# IO.net
KiCad netlist of a schematic drawn in Altium Designer
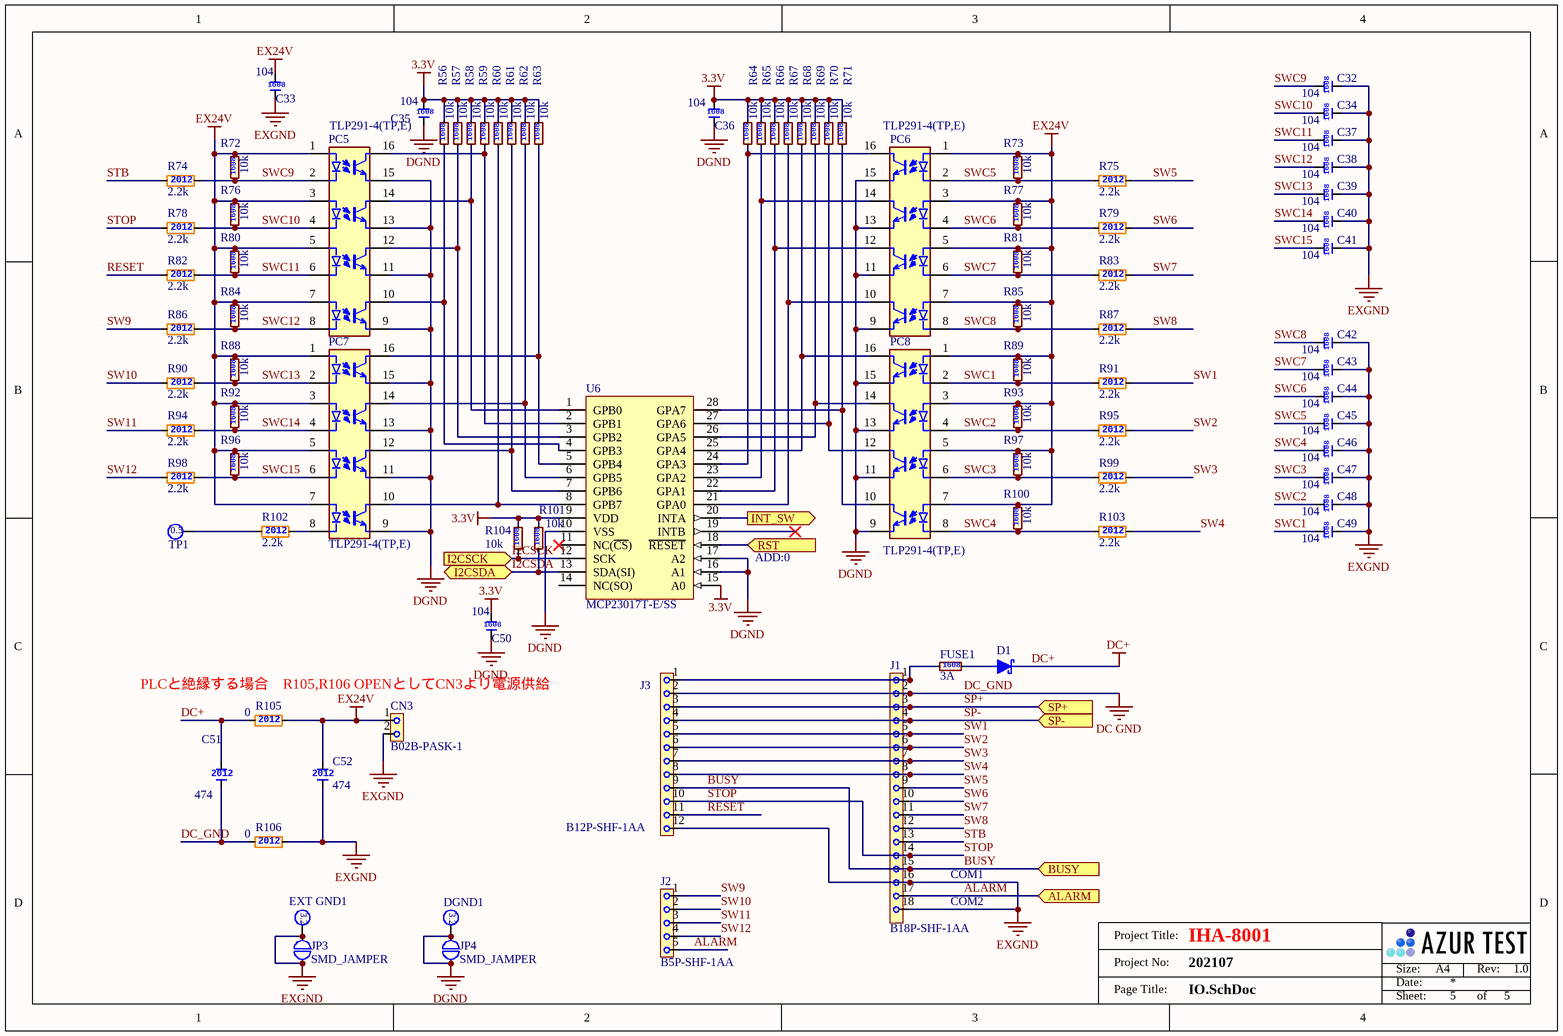
[diagram p0: IO.SchDoc]

(export (version "E")
  (design (tool "Eeschema 10.0.6"))
  (components
    (comp (ref "C32")
      (value "CGA3E2X7R1H104K080AA")
      (footprint "C1608")
      (description "セラコン1608サイズ")
      (fields (field (name "TAG") "104") (field (name "VOLTAGE") "50V"))
      (libsource (lib "Audio") (part "C1608"))
    )
    (comp (ref "C33")
      (value "CGA3E2X7R1H104K080AA")
      (footprint "C1608")
      (description "セラコン1608サイズ")
      (fields (field (name "TAG") "104") (field (name "VOLTAGE") "50V"))
      (libsource (lib "Audio") (part "C1608"))
    )
    (comp (ref "C34")
      (value "CGA3E2X7R1H104K080AA")
      (footprint "C1608")
      (description "セラコン1608サイズ")
      (fields (field (name "TAG") "104") (field (name "VOLTAGE") "50V"))
      (libsource (lib "Audio") (part "C1608"))
    )
    (comp (ref "C35")
      (value "CGA3E2X7R1H104K080AA")
      (footprint "C1608")
      (description "セラコン1608サイズ")
      (fields (field (name "TAG") "104") (field (name "VOLTAGE") "50V"))
      (libsource (lib "Audio") (part "C1608"))
    )
    (comp (ref "C36")
      (value "CGA3E2X7R1H104K080AA")
      (footprint "C1608")
      (description "セラコン1608サイズ")
      (fields (field (name "TAG") "104") (field (name "VOLTAGE") "50V"))
      (libsource (lib "Audio") (part "C1608"))
    )
    (comp (ref "C37")
      (value "CGA3E2X7R1H104K080AA")
      (footprint "C1608")
      (description "セラコン1608サイズ")
      (fields (field (name "TAG") "104") (field (name "VOLTAGE") "50V"))
      (libsource (lib "Audio") (part "C1608"))
    )
    (comp (ref "C38")
      (value "CGA3E2X7R1H104K080AA")
      (footprint "C1608")
      (description "セラコン1608サイズ")
      (fields (field (name "TAG") "104") (field (name "VOLTAGE") "50V"))
      (libsource (lib "Audio") (part "C1608"))
    )
    (comp (ref "C39")
      (value "CGA3E2X7R1H104K080AA")
      (footprint "C1608")
      (description "セラコン1608サイズ")
      (fields (field (name "TAG") "104") (field (name "VOLTAGE") "50V"))
      (libsource (lib "Audio") (part "C1608"))
    )
    (comp (ref "C40")
      (value "CGA3E2X7R1H104K080AA")
      (footprint "C1608")
      (description "セラコン1608サイズ")
      (fields (field (name "TAG") "104") (field (name "VOLTAGE") "50V"))
      (libsource (lib "Audio") (part "C1608"))
    )
    (comp (ref "C41")
      (value "CGA3E2X7R1H104K080AA")
      (footprint "C1608")
      (description "セラコン1608サイズ")
      (fields (field (name "TAG") "104") (field (name "VOLTAGE") "50V"))
      (libsource (lib "Audio") (part "C1608"))
    )
    (comp (ref "C42")
      (value "CGA3E2X7R1H104K080AA")
      (footprint "C1608")
      (description "セラコン1608サイズ")
      (fields (field (name "TAG") "104") (field (name "VOLTAGE") "50V"))
      (libsource (lib "Audio") (part "C1608"))
    )
    (comp (ref "C43")
      (value "CGA3E2X7R1H104K080AA")
      (footprint "C1608")
      (description "セラコン1608サイズ")
      (fields (field (name "TAG") "104") (field (name "VOLTAGE") "50V"))
      (libsource (lib "Audio") (part "C1608"))
    )
    (comp (ref "C44")
      (value "CGA3E2X7R1H104K080AA")
      (footprint "C1608")
      (description "セラコン1608サイズ")
      (fields (field (name "TAG") "104") (field (name "VOLTAGE") "50V"))
      (libsource (lib "Audio") (part "C1608"))
    )
    (comp (ref "C45")
      (value "CGA3E2X7R1H104K080AA")
      (footprint "C1608")
      (description "セラコン1608サイズ")
      (fields (field (name "TAG") "104") (field (name "VOLTAGE") "50V"))
      (libsource (lib "Audio") (part "C1608"))
    )
    (comp (ref "C46")
      (value "CGA3E2X7R1H104K080AA")
      (footprint "C1608")
      (description "セラコン1608サイズ")
      (fields (field (name "TAG") "104") (field (name "VOLTAGE") "50V"))
      (libsource (lib "Audio") (part "C1608"))
    )
    (comp (ref "C47")
      (value "CGA3E2X7R1H104K080AA")
      (footprint "C1608")
      (description "セラコン1608サイズ")
      (fields (field (name "TAG") "104") (field (name "VOLTAGE") "50V"))
      (libsource (lib "Audio") (part "C1608"))
    )
    (comp (ref "C48")
      (value "CGA3E2X7R1H104K080AA")
      (footprint "C1608")
      (description "セラコン1608サイズ")
      (fields (field (name "TAG") "104") (field (name "VOLTAGE") "50V"))
      (libsource (lib "Audio") (part "C1608"))
    )
    (comp (ref "C49")
      (value "CGA3E2X7R1H104K080AA")
      (footprint "C1608")
      (description "セラコン1608サイズ")
      (fields (field (name "TAG") "104") (field (name "VOLTAGE") "50V"))
      (libsource (lib "Audio") (part "C1608"))
    )
    (comp (ref "C50")
      (value "CGA3E2X7R1H104K080AA")
      (footprint "C1608")
      (description "セラコン1608サイズ")
      (fields (field (name "TAG") "104") (field (name "VOLTAGE") "50V"))
      (libsource (lib "Audio") (part "C1608"))
    )
    (comp (ref "C51")
      (value "GRM21BR71H474MA88")
      (footprint "C2012")
      (description "セラコン2012サイズ")
      (fields (field (name "TAG") "474") (field (name "VOLTAGE") "50V"))
      (libsource (lib "Audio") (part "C2012"))
    )
    (comp (ref "C52")
      (value "GRM21BR71H474MA88")
      (footprint "C2012")
      (description "セラコン2012サイズ")
      (fields (field (name "TAG") "474") (field (name "VOLTAGE") "50V"))
      (libsource (lib "Audio") (part "C2012"))
    )
    (comp (ref "CN3")
      (value "B02B-PASK-1")
      (footprint "B02B-PASK-1")
      (description "雄,ストレート,1列2ピン")
      (libsource (lib "Audio Prj") (part "B02B-PASK-1"))
    )
    (comp (ref "D1")
      (value "SIPS3150U")
      (footprint "DO-214AA")
      (description "Schottky Rectifier")
      (fields (field (name "VOLTAGE") "150V"))
      (libsource (lib "Audio") (part "Diode SMB 5.4x4.3"))
    )
    (comp (ref "DGND1")
      (value "TP3.2mm")
      (footprint "TP3.2mm")
      (description "Test-Point 3.2mm")
      (libsource (lib "Audio Prj") (part "TP3.2mm"))
    )
    (comp (ref "EXT GND1")
      (value "TP3.2mm")
      (footprint "TP3.2mm")
      (description "Test-Point 3.2mm")
      (libsource (lib "Audio Prj") (part "TP3.2mm"))
    )
    (comp (ref "FUSE1")
      (value "ERB-RE3R00V")
      (footprint "R1608")
      (description "3A 1608サイズ")
      (fields (field (name "TAG") "3A"))
      (libsource (lib "") (part "TF1608_1"))
    )
    (comp (ref "J1")
      (value "B18P-SHF-1AA")
      (footprint "B18P-SHF-1AA")
      (description "雄,ストレート,1列12ピン PCB")
      (libsource (lib "Audio Prj") (part "B18P-SHF-1AA"))
    )
    (comp (ref "J2")
      (value "B5P-SHF-1AA")
      (footprint "B5P-SHF-1AA")
      (description "雄,ストレート,1列3ピン")
      (libsource (lib "Audio Prj") (part "B5P-SHF-1AA"))
    )
    (comp (ref "J3")
      (value "B12P-SHF-1AA")
      (footprint "B12P-SHF-1AA")
      (description "雄,ストレート,1列12ピン PCB")
      (libsource (lib "Audio") (part "B12P-SHF-1AA"))
    )
    (comp (ref "JP3")
      (value "SMD_JAMPER")
      (footprint "SMD_JAMPER -Cut")
      (libsource (lib "Audio") (part "SMD_JAMPER"))
    )
    (comp (ref "JP4")
      (value "SMD_JAMPER")
      (footprint "SMD_JAMPER -Cut")
      (libsource (lib "Audio") (part "SMD_JAMPER"))
    )
    (comp (ref "PC5")
      (value "TLP291-4(TP,E)")
      (footprint "SO16")
      (description "4 Channel 16-SO")
      (libsource (lib "Audio Prj") (part "TLP293-4"))
    )
    (comp (ref "PC6")
      (value "TLP291-4(TP,E)")
      (footprint "SO16")
      (description "4 Channel 16-SO")
      (libsource (lib "Audio Prj") (part "TLP293-4"))
    )
    (comp (ref "PC7")
      (value "TLP291-4(TP,E)")
      (footprint "SO16")
      (description "4 Channel 16-SO")
      (libsource (lib "Audio Prj") (part "TLP293-4"))
    )
    (comp (ref "PC8")
      (value "TLP291-4(TP,E)")
      (footprint "SO16")
      (description "4 Channel 16-SO")
      (libsource (lib "Audio Prj") (part "TLP293-4"))
    )
    (comp (ref "R56")
      (value "ERJ-PA3F1002V")
      (footprint "R1608")
      (description "厚膜チップ抵抗1608サイズ")
      (fields (field (name "TAG") "10k"))
      (libsource (lib "Schlib1") (part "TF1608"))
    )
    (comp (ref "R57")
      (value "ERJ-PA3F1002V")
      (footprint "R1608")
      (description "厚膜チップ抵抗1608サイズ")
      (fields (field (name "TAG") "10k"))
      (libsource (lib "Schlib1") (part "TF1608"))
    )
    (comp (ref "R58")
      (value "ERJ-PA3F1002V")
      (footprint "R1608")
      (description "厚膜チップ抵抗1608サイズ")
      (fields (field (name "TAG") "10k"))
      (libsource (lib "Schlib1") (part "TF1608"))
    )
    (comp (ref "R59")
      (value "ERJ-PA3F1002V")
      (footprint "R1608")
      (description "厚膜チップ抵抗1608サイズ")
      (fields (field (name "TAG") "10k"))
      (libsource (lib "Schlib1") (part "TF1608"))
    )
    (comp (ref "R60")
      (value "ERJ-PA3F1002V")
      (footprint "R1608")
      (description "厚膜チップ抵抗1608サイズ")
      (fields (field (name "TAG") "10k"))
      (libsource (lib "Schlib1") (part "TF1608"))
    )
    (comp (ref "R61")
      (value "ERJ-PA3F1002V")
      (footprint "R1608")
      (description "厚膜チップ抵抗1608サイズ")
      (fields (field (name "TAG") "10k"))
      (libsource (lib "Schlib1") (part "TF1608"))
    )
    (comp (ref "R62")
      (value "ERJ-PA3F1002V")
      (footprint "R1608")
      (description "厚膜チップ抵抗1608サイズ")
      (fields (field (name "TAG") "10k"))
      (libsource (lib "Schlib1") (part "TF1608"))
    )
    (comp (ref "R63")
      (value "ERJ-PA3F1002V")
      (footprint "R1608")
      (description "厚膜チップ抵抗1608サイズ")
      (fields (field (name "TAG") "10k"))
      (libsource (lib "Schlib1") (part "TF1608"))
    )
    (comp (ref "R64")
      (value "ERJ-PA3F1002V")
      (footprint "R1608")
      (description "厚膜チップ抵抗1608サイズ")
      (fields (field (name "TAG") "10k"))
      (libsource (lib "Schlib1") (part "TF1608"))
    )
    (comp (ref "R65")
      (value "ERJ-PA3F1002V")
      (footprint "R1608")
      (description "厚膜チップ抵抗1608サイズ")
      (fields (field (name "TAG") "10k"))
      (libsource (lib "Schlib1") (part "TF1608"))
    )
    (comp (ref "R66")
      (value "ERJ-PA3F1002V")
      (footprint "R1608")
      (description "厚膜チップ抵抗1608サイズ")
      (fields (field (name "TAG") "10k"))
      (libsource (lib "Schlib1") (part "TF1608"))
    )
    (comp (ref "R67")
      (value "ERJ-PA3F1002V")
      (footprint "R1608")
      (description "厚膜チップ抵抗1608サイズ")
      (fields (field (name "TAG") "10k"))
      (libsource (lib "Schlib1") (part "TF1608"))
    )
    (comp (ref "R68")
      (value "ERJ-PA3F1002V")
      (footprint "R1608")
      (description "厚膜チップ抵抗1608サイズ")
      (fields (field (name "TAG") "10k"))
      (libsource (lib "Schlib1") (part "TF1608"))
    )
    (comp (ref "R69")
      (value "ERJ-PA3F1002V")
      (footprint "R1608")
      (description "厚膜チップ抵抗1608サイズ")
      (fields (field (name "TAG") "10k"))
      (libsource (lib "Schlib1") (part "TF1608"))
    )
    (comp (ref "R70")
      (value "ERJ-PA3F1002V")
      (footprint "R1608")
      (description "厚膜チップ抵抗1608サイズ")
      (fields (field (name "TAG") "10k"))
      (libsource (lib "Schlib1") (part "TF1608"))
    )
    (comp (ref "R71")
      (value "ERJ-PA3F1002V")
      (footprint "R1608")
      (description "厚膜チップ抵抗1608サイズ")
      (fields (field (name "TAG") "10k"))
      (libsource (lib "Schlib1") (part "TF1608"))
    )
    (comp (ref "R72")
      (value "ERJ-PA3F1002V")
      (footprint "R1608")
      (description "厚膜チップ抵抗1608サイズ")
      (fields (field (name "TAG") "10k"))
      (libsource (lib "Schlib1") (part "TF1608"))
    )
    (comp (ref "R73")
      (value "ERJ-PA3F1002V")
      (footprint "R1608")
      (description "厚膜チップ抵抗1608サイズ")
      (fields (field (name "TAG") "10k"))
      (libsource (lib "Schlib1") (part "TF1608"))
    )
    (comp (ref "R74")
      (value "ERJ-P08J222V")
      (footprint "R2012")
      (description "薄膜チップ抵抗2012サイズ")
      (fields (field (name "TAG") "2.2k"))
      (libsource (lib "Audio") (part "MF2012"))
    )
    (comp (ref "R75")
      (value "ERJ-P08J222V")
      (footprint "R2012")
      (description "薄膜チップ抵抗2012サイズ")
      (fields (field (name "TAG") "2.2k"))
      (libsource (lib "Audio") (part "MF2012"))
    )
    (comp (ref "R76")
      (value "ERJ-PA3F1002V")
      (footprint "R1608")
      (description "厚膜チップ抵抗1608サイズ")
      (fields (field (name "TAG") "10k"))
      (libsource (lib "Schlib1") (part "TF1608"))
    )
    (comp (ref "R77")
      (value "ERJ-PA3F1002V")
      (footprint "R1608")
      (description "厚膜チップ抵抗1608サイズ")
      (fields (field (name "TAG") "10k"))
      (libsource (lib "Schlib1") (part "TF1608"))
    )
    (comp (ref "R78")
      (value "ERJ-P08J222V")
      (footprint "R2012")
      (description "薄膜チップ抵抗2012サイズ")
      (fields (field (name "TAG") "2.2k"))
      (libsource (lib "Audio") (part "MF2012"))
    )
    (comp (ref "R79")
      (value "ERJ-P08J222V")
      (footprint "R2012")
      (description "薄膜チップ抵抗2012サイズ")
      (fields (field (name "TAG") "2.2k"))
      (libsource (lib "Audio") (part "MF2012"))
    )
    (comp (ref "R80")
      (value "ERJ-PA3F1002V")
      (footprint "R1608")
      (description "厚膜チップ抵抗1608サイズ")
      (fields (field (name "TAG") "10k"))
      (libsource (lib "Schlib1") (part "TF1608"))
    )
    (comp (ref "R81")
      (value "ERJ-PA3F1002V")
      (footprint "R1608")
      (description "厚膜チップ抵抗1608サイズ")
      (fields (field (name "TAG") "10k"))
      (libsource (lib "Schlib1") (part "TF1608"))
    )
    (comp (ref "R82")
      (value "ERJ-P08J222V")
      (footprint "R2012")
      (description "薄膜チップ抵抗2012サイズ")
      (fields (field (name "TAG") "2.2k"))
      (libsource (lib "Audio") (part "MF2012"))
    )
    (comp (ref "R83")
      (value "ERJ-P08J222V")
      (footprint "R2012")
      (description "薄膜チップ抵抗2012サイズ")
      (fields (field (name "TAG") "2.2k"))
      (libsource (lib "Audio") (part "MF2012"))
    )
    (comp (ref "R84")
      (value "ERJ-PA3F1002V")
      (footprint "R1608")
      (description "厚膜チップ抵抗1608サイズ")
      (fields (field (name "TAG") "10k"))
      (libsource (lib "Schlib1") (part "TF1608"))
    )
    (comp (ref "R85")
      (value "ERJ-PA3F1002V")
      (footprint "R1608")
      (description "厚膜チップ抵抗1608サイズ")
      (fields (field (name "TAG") "10k"))
      (libsource (lib "Schlib1") (part "TF1608"))
    )
    (comp (ref "R86")
      (value "ERJ-P08J222V")
      (footprint "R2012")
      (description "薄膜チップ抵抗2012サイズ")
      (fields (field (name "TAG") "2.2k"))
      (libsource (lib "Audio") (part "MF2012"))
    )
    (comp (ref "R87")
      (value "ERJ-P08J222V")
      (footprint "R2012")
      (description "薄膜チップ抵抗2012サイズ")
      (fields (field (name "TAG") "2.2k"))
      (libsource (lib "Audio") (part "MF2012"))
    )
    (comp (ref "R88")
      (value "ERJ-PA3F1002V")
      (footprint "R1608")
      (description "厚膜チップ抵抗1608サイズ")
      (fields (field (name "TAG") "10k"))
      (libsource (lib "Schlib1") (part "TF1608"))
    )
    (comp (ref "R89")
      (value "ERJ-PA3F1002V")
      (footprint "R1608")
      (description "厚膜チップ抵抗1608サイズ")
      (fields (field (name "TAG") "10k"))
      (libsource (lib "Schlib1") (part "TF1608"))
    )
    (comp (ref "R90")
      (value "ERJ-P08J222V")
      (footprint "R2012")
      (description "薄膜チップ抵抗2012サイズ")
      (fields (field (name "TAG") "2.2k"))
      (libsource (lib "Audio") (part "MF2012"))
    )
    (comp (ref "R91")
      (value "ERJ-P08J222V")
      (footprint "R2012")
      (description "薄膜チップ抵抗2012サイズ")
      (fields (field (name "TAG") "2.2k"))
      (libsource (lib "Audio") (part "MF2012"))
    )
    (comp (ref "R92")
      (value "ERJ-PA3F1002V")
      (footprint "R1608")
      (description "厚膜チップ抵抗1608サイズ")
      (fields (field (name "TAG") "10k"))
      (libsource (lib "Schlib1") (part "TF1608"))
    )
    (comp (ref "R93")
      (value "ERJ-PA3F1002V")
      (footprint "R1608")
      (description "厚膜チップ抵抗1608サイズ")
      (fields (field (name "TAG") "10k"))
      (libsource (lib "Schlib1") (part "TF1608"))
    )
    (comp (ref "R94")
      (value "ERJ-P08J222V")
      (footprint "R2012")
      (description "薄膜チップ抵抗2012サイズ")
      (fields (field (name "TAG") "2.2k"))
      (libsource (lib "Audio") (part "MF2012"))
    )
    (comp (ref "R95")
      (value "ERJ-P08J222V")
      (footprint "R2012")
      (description "薄膜チップ抵抗2012サイズ")
      (fields (field (name "TAG") "2.2k"))
      (libsource (lib "Audio") (part "MF2012"))
    )
    (comp (ref "R96")
      (value "ERJ-PA3F1002V")
      (footprint "R1608")
      (description "厚膜チップ抵抗1608サイズ")
      (fields (field (name "TAG") "10k"))
      (libsource (lib "Schlib1") (part "TF1608"))
    )
    (comp (ref "R97")
      (value "ERJ-PA3F1002V")
      (footprint "R1608")
      (description "厚膜チップ抵抗1608サイズ")
      (fields (field (name "TAG") "10k"))
      (libsource (lib "Schlib1") (part "TF1608"))
    )
    (comp (ref "R98")
      (value "ERJ-P08J222V")
      (footprint "R2012")
      (description "薄膜チップ抵抗2012サイズ")
      (fields (field (name "TAG") "2.2k"))
      (libsource (lib "Audio") (part "MF2012"))
    )
    (comp (ref "R99")
      (value "ERJ-P08J222V")
      (footprint "R2012")
      (description "薄膜チップ抵抗2012サイズ")
      (fields (field (name "TAG") "2.2k"))
      (libsource (lib "Audio") (part "MF2012"))
    )
    (comp (ref "R100")
      (value "ERJ-PA3F1002V")
      (footprint "R1608")
      (description "厚膜チップ抵抗1608サイズ")
      (fields (field (name "TAG") "10k"))
      (libsource (lib "Schlib1") (part "TF1608"))
    )
    (comp (ref "R101")
      (value "ERJ-PA3F1002V")
      (footprint "R1608")
      (description "厚膜チップ抵抗1608サイズ")
      (fields (field (name "TAG") "10k"))
      (libsource (lib "Schlib1") (part "TF1608"))
    )
    (comp (ref "R102")
      (value "ERJ-P08J222V")
      (footprint "R2012")
      (description "薄膜チップ抵抗2012サイズ")
      (fields (field (name "TAG") "2.2k"))
      (libsource (lib "Audio") (part "MF2012"))
    )
    (comp (ref "R103")
      (value "ERJ-P08J222V")
      (footprint "R2012")
      (description "薄膜チップ抵抗2012サイズ")
      (fields (field (name "TAG") "2.2k"))
      (libsource (lib "Audio") (part "MF2012"))
    )
    (comp (ref "R104")
      (value "ERJ-PA3F1002V")
      (footprint "R1608")
      (description "厚膜チップ抵抗1608サイズ")
      (fields (field (name "TAG") "10k"))
      (libsource (lib "Schlib1") (part "TF1608"))
    )
    (comp (ref "R105")
      (value "ERJ-6GEY0R00V")
      (footprint "R2012")
      (description "薄膜チップ抵抗2012サイズ")
      (fields (field (name "TAG") "0"))
      (libsource (lib "Audio") (part "MF2012"))
    )
    (comp (ref "R106")
      (value "ERJ-6GEY0R00V")
      (footprint "R2012")
      (description "薄膜チップ抵抗2012サイズ")
      (fields (field (name "TAG") "0"))
      (libsource (lib "Audio") (part "MF2012"))
    )
    (comp (ref "TP1")
      (value "TP0.5mm")
      (footprint "TP0.5mm")
      (description "Test-Point 0.5mm")
      (libsource (lib "Audio") (part "TP0.5mm"))
    )
    (comp (ref "U6")
      (value "MCP23017T-E/SS")
      (footprint "SSOP28")
      (description "I/O Expander 16 SPI 10MHz 28-SOIC")
      (libsource (lib "Audio Prj") (part "MCP23_17T-E/SO"))
    )
  )
  (nets
    (net (code "1") (name "/ALARM") (class "Default")
      (node (ref "J1") (pin "17") (pinfunction "17_17") (pintype "passive"))
      (node (ref "J2") (pin "5") (pinfunction "5_5") (pintype "passive"))
    )
    (net (code "2") (name "/BUSY") (class "Default")
      (node (ref "J1") (pin "15") (pinfunction "15_15") (pintype "passive"))
      (node (ref "J3") (pin "9") (pinfunction "9_9") (pintype "passive"))
    )
    (net (code "3") (name "/I2CSCK") (class "Default")
      (node (ref "R104") (pin "1") (pinfunction "1_1") (pintype "passive"))
      (node (ref "U6") (pin "12") (pinfunction "SCK_12") (pintype "passive"))
    )
    (net (code "4") (name "/I2CSDA") (class "Default")
      (node (ref "R101") (pin "1") (pinfunction "1_1") (pintype "passive"))
      (node (ref "U6") (pin "13") (pinfunction "SDA(SI)_13") (pintype "passive"))
    )
    (net (code "5") (name "/INT_SW") (class "Default")
      (node (ref "U6") (pin "20") (pinfunction "INTA_20") (pintype "output"))
    )
    (net (code "6") (name "/RESET") (class "Default")
      (node (ref "J3") (pin "11") (pinfunction "11_11") (pintype "passive"))
      (node (ref "R82") (pin "1") (pinfunction "1_1") (pintype "passive"))
    )
    (net (code "7") (name "/RST") (class "Default")
      (node (ref "U6") (pin "18") (pinfunction "~{RESET}_18") (pintype "input"))
    )
    (net (code "8") (name "/SP+") (class "Default")
      (node (ref "J1") (pin "3") (pinfunction "3_3") (pintype "passive"))
      (node (ref "J3") (pin "3") (pinfunction "3_3") (pintype "passive"))
    )
    (net (code "9") (name "/SP-") (class "Default")
      (node (ref "J1") (pin "4") (pinfunction "4_4") (pintype "passive"))
      (node (ref "J3") (pin "4") (pinfunction "4_4") (pintype "passive"))
    )
    (net (code "10") (name "/STB") (class "Default")
      (node (ref "J1") (pin "13") (pinfunction "13_13") (pintype "passive"))
      (node (ref "R74") (pin "1") (pinfunction "1_1") (pintype "passive"))
    )
    (net (code "11") (name "/STOP") (class "Default")
      (node (ref "J1") (pin "14") (pinfunction "14_14") (pintype "passive"))
      (node (ref "J3") (pin "10") (pinfunction "10_10") (pintype "passive"))
      (node (ref "R78") (pin "1") (pinfunction "1_1") (pintype "passive"))
    )
    (net (code "12") (name "/SW1") (class "Default")
      (node (ref "J1") (pin "5") (pinfunction "5_5") (pintype "passive"))
      (node (ref "J3") (pin "5") (pinfunction "5_5") (pintype "passive"))
      (node (ref "R91") (pin "2") (pinfunction "2_2") (pintype "passive"))
    )
    (net (code "13") (name "/SW2") (class "Default")
      (node (ref "J1") (pin "6") (pinfunction "6_6") (pintype "passive"))
      (node (ref "J3") (pin "6") (pinfunction "6_6") (pintype "passive"))
      (node (ref "R95") (pin "2") (pinfunction "2_2") (pintype "passive"))
    )
    (net (code "14") (name "/SW3") (class "Default")
      (node (ref "J1") (pin "7") (pinfunction "7_7") (pintype "passive"))
      (node (ref "J3") (pin "7") (pinfunction "7_7") (pintype "passive"))
      (node (ref "R99") (pin "2") (pinfunction "2_2") (pintype "passive"))
    )
    (net (code "15") (name "/SW4") (class "Default")
      (node (ref "J1") (pin "8") (pinfunction "8_8") (pintype "passive"))
      (node (ref "J3") (pin "8") (pinfunction "8_8") (pintype "passive"))
      (node (ref "R103") (pin "2") (pinfunction "2_2") (pintype "passive"))
    )
    (net (code "16") (name "/SW5") (class "Default")
      (node (ref "J1") (pin "9") (pinfunction "9_9") (pintype "passive"))
      (node (ref "R75") (pin "2") (pinfunction "2_2") (pintype "passive"))
    )
    (net (code "17") (name "/SW6") (class "Default")
      (node (ref "J1") (pin "10") (pinfunction "10_10") (pintype "passive"))
      (node (ref "R79") (pin "2") (pinfunction "2_2") (pintype "passive"))
    )
    (net (code "18") (name "/SW7") (class "Default")
      (node (ref "J1") (pin "11") (pinfunction "11_11") (pintype "passive"))
      (node (ref "R83") (pin "2") (pinfunction "2_2") (pintype "passive"))
    )
    (net (code "19") (name "/SW8") (class "Default")
      (node (ref "J1") (pin "12") (pinfunction "12_12") (pintype "passive"))
      (node (ref "R87") (pin "2") (pinfunction "2_2") (pintype "passive"))
    )
    (net (code "20") (name "/SW9") (class "Default")
      (node (ref "J2") (pin "1") (pinfunction "1_1") (pintype "passive"))
      (node (ref "R86") (pin "1") (pinfunction "1_1") (pintype "passive"))
    )
    (net (code "21") (name "/SW10") (class "Default")
      (node (ref "J2") (pin "2") (pinfunction "2_2") (pintype "passive"))
      (node (ref "R90") (pin "1") (pinfunction "1_1") (pintype "passive"))
    )
    (net (code "22") (name "/SW11") (class "Default")
      (node (ref "J2") (pin "3") (pinfunction "3_3") (pintype "passive"))
      (node (ref "R94") (pin "1") (pinfunction "1_1") (pintype "passive"))
    )
    (net (code "23") (name "/SW12") (class "Default")
      (node (ref "J2") (pin "4") (pinfunction "4_4") (pintype "passive"))
      (node (ref "R98") (pin "1") (pinfunction "1_1") (pintype "passive"))
    )
    (net (code "24") (name "/SWC1") (class "Default")
      (node (ref "C49") (pin "2") (pinfunction "2_2") (pintype "passive"))
      (node (ref "PC8") (pin "2") (pinfunction "K-LED_2") (pintype "passive"))
      (node (ref "R89") (pin "1") (pinfunction "1_1") (pintype "passive"))
      (node (ref "R91") (pin "1") (pinfunction "1_1") (pintype "passive"))
    )
    (net (code "25") (name "/SWC2") (class "Default")
      (node (ref "C48") (pin "2") (pinfunction "2_2") (pintype "passive"))
      (node (ref "PC8") (pin "4") (pinfunction "K-LED_4") (pintype "passive"))
      (node (ref "R93") (pin "1") (pinfunction "1_1") (pintype "passive"))
      (node (ref "R95") (pin "1") (pinfunction "1_1") (pintype "passive"))
    )
    (net (code "26") (name "/SWC3") (class "Default")
      (node (ref "C47") (pin "2") (pinfunction "2_2") (pintype "passive"))
      (node (ref "PC8") (pin "6") (pinfunction "K-LED_6") (pintype "passive"))
      (node (ref "R97") (pin "1") (pinfunction "1_1") (pintype "passive"))
      (node (ref "R99") (pin "1") (pinfunction "1_1") (pintype "passive"))
    )
    (net (code "27") (name "/SWC4") (class "Default")
      (node (ref "C46") (pin "2") (pinfunction "2_2") (pintype "passive"))
      (node (ref "PC8") (pin "8") (pinfunction "K-LED_8") (pintype "passive"))
      (node (ref "R100") (pin "1") (pinfunction "1_1") (pintype "passive"))
      (node (ref "R103") (pin "1") (pinfunction "1_1") (pintype "passive"))
    )
    (net (code "28") (name "/SWC5") (class "Default")
      (node (ref "C45") (pin "2") (pinfunction "2_2") (pintype "passive"))
      (node (ref "PC6") (pin "2") (pinfunction "K-LED_2") (pintype "passive"))
      (node (ref "R73") (pin "1") (pinfunction "1_1") (pintype "passive"))
      (node (ref "R75") (pin "1") (pinfunction "1_1") (pintype "passive"))
    )
    (net (code "29") (name "/SWC6") (class "Default")
      (node (ref "C44") (pin "2") (pinfunction "2_2") (pintype "passive"))
      (node (ref "PC6") (pin "4") (pinfunction "K-LED_4") (pintype "passive"))
      (node (ref "R77") (pin "1") (pinfunction "1_1") (pintype "passive"))
      (node (ref "R79") (pin "1") (pinfunction "1_1") (pintype "passive"))
    )
    (net (code "30") (name "/SWC7") (class "Default")
      (node (ref "C43") (pin "2") (pinfunction "2_2") (pintype "passive"))
      (node (ref "PC6") (pin "6") (pinfunction "K-LED_6") (pintype "passive"))
      (node (ref "R81") (pin "1") (pinfunction "1_1") (pintype "passive"))
      (node (ref "R83") (pin "1") (pinfunction "1_1") (pintype "passive"))
    )
    (net (code "31") (name "/SWC8") (class "Default")
      (node (ref "C42") (pin "2") (pinfunction "2_2") (pintype "passive"))
      (node (ref "PC6") (pin "8") (pinfunction "K-LED_8") (pintype "passive"))
      (node (ref "R85") (pin "1") (pinfunction "1_1") (pintype "passive"))
      (node (ref "R87") (pin "1") (pinfunction "1_1") (pintype "passive"))
    )
    (net (code "32") (name "/SWC9") (class "Default")
      (node (ref "C32") (pin "2") (pinfunction "2_2") (pintype "passive"))
      (node (ref "PC5") (pin "2") (pinfunction "K-LED_2") (pintype "passive"))
      (node (ref "R72") (pin "1") (pinfunction "1_1") (pintype "passive"))
      (node (ref "R74") (pin "2") (pinfunction "2_2") (pintype "passive"))
    )
    (net (code "33") (name "/SWC10") (class "Default")
      (node (ref "C34") (pin "2") (pinfunction "2_2") (pintype "passive"))
      (node (ref "PC5") (pin "4") (pinfunction "K-LED_4") (pintype "passive"))
      (node (ref "R76") (pin "1") (pinfunction "1_1") (pintype "passive"))
      (node (ref "R78") (pin "2") (pinfunction "2_2") (pintype "passive"))
    )
    (net (code "34") (name "/SWC11") (class "Default")
      (node (ref "C37") (pin "2") (pinfunction "2_2") (pintype "passive"))
      (node (ref "PC5") (pin "6") (pinfunction "K-LED_6") (pintype "passive"))
      (node (ref "R80") (pin "1") (pinfunction "1_1") (pintype "passive"))
      (node (ref "R82") (pin "2") (pinfunction "2_2") (pintype "passive"))
    )
    (net (code "35") (name "/SWC12") (class "Default")
      (node (ref "C38") (pin "2") (pinfunction "2_2") (pintype "passive"))
      (node (ref "PC5") (pin "8") (pinfunction "K-LED_8") (pintype "passive"))
      (node (ref "R84") (pin "1") (pinfunction "1_1") (pintype "passive"))
      (node (ref "R86") (pin "2") (pinfunction "2_2") (pintype "passive"))
    )
    (net (code "36") (name "/SWC13") (class "Default")
      (node (ref "C39") (pin "2") (pinfunction "2_2") (pintype "passive"))
      (node (ref "PC7") (pin "2") (pinfunction "K-LED_2") (pintype "passive"))
      (node (ref "R88") (pin "1") (pinfunction "1_1") (pintype "passive"))
      (node (ref "R90") (pin "2") (pinfunction "2_2") (pintype "passive"))
    )
    (net (code "37") (name "/SWC14") (class "Default")
      (node (ref "C40") (pin "2") (pinfunction "2_2") (pintype "passive"))
      (node (ref "PC7") (pin "4") (pinfunction "K-LED_4") (pintype "passive"))
      (node (ref "R92") (pin "1") (pinfunction "1_1") (pintype "passive"))
      (node (ref "R94") (pin "2") (pinfunction "2_2") (pintype "passive"))
    )
    (net (code "38") (name "/SWC15") (class "Default")
      (node (ref "C41") (pin "2") (pinfunction "2_2") (pintype "passive"))
      (node (ref "PC7") (pin "6") (pinfunction "K-LED_6") (pintype "passive"))
      (node (ref "R96") (pin "1") (pinfunction "1_1") (pintype "passive"))
      (node (ref "R98") (pin "2") (pinfunction "2_2") (pintype "passive"))
    )
    (net (code "39") (name "3.3V") (class "Default")
      (node (ref "C35") (pin "2") (pinfunction "2_2") (pintype "passive"))
      (node (ref "C36") (pin "2") (pinfunction "2_2") (pintype "passive"))
      (node (ref "C50") (pin "2") (pinfunction "2_2") (pintype "passive"))
      (node (ref "R101") (pin "2") (pinfunction "2_2") (pintype "passive"))
      (node (ref "R104") (pin "2") (pinfunction "2_2") (pintype "passive"))
      (node (ref "R56") (pin "2") (pinfunction "2_2") (pintype "passive"))
      (node (ref "R57") (pin "2") (pinfunction "2_2") (pintype "passive"))
      (node (ref "R58") (pin "2") (pinfunction "2_2") (pintype "passive"))
      (node (ref "R59") (pin "2") (pinfunction "2_2") (pintype "passive"))
      (node (ref "R60") (pin "2") (pinfunction "2_2") (pintype "passive"))
      (node (ref "R61") (pin "2") (pinfunction "2_2") (pintype "passive"))
      (node (ref "R62") (pin "2") (pinfunction "2_2") (pintype "passive"))
      (node (ref "R63") (pin "2") (pinfunction "2_2") (pintype "passive"))
      (node (ref "R64") (pin "2") (pinfunction "2_2") (pintype "passive"))
      (node (ref "R65") (pin "2") (pinfunction "2_2") (pintype "passive"))
      (node (ref "R66") (pin "2") (pinfunction "2_2") (pintype "passive"))
      (node (ref "R67") (pin "2") (pinfunction "2_2") (pintype "passive"))
      (node (ref "R68") (pin "2") (pinfunction "2_2") (pintype "passive"))
      (node (ref "R69") (pin "2") (pinfunction "2_2") (pintype "passive"))
      (node (ref "R70") (pin "2") (pinfunction "2_2") (pintype "passive"))
      (node (ref "R71") (pin "2") (pinfunction "2_2") (pintype "passive"))
      (node (ref "U6") (pin "15") (pinfunction "A0_15") (pintype "input"))
      (node (ref "U6") (pin "9") (pinfunction "VDD_9") (pintype "power_in"))
    )
    (net (code "40") (name "DC GND") (class "Default")
      (node (ref "C51") (pin "1") (pinfunction "1_1") (pintype "passive"))
      (node (ref "J1") (pin "2") (pinfunction "2_2") (pintype "passive"))
      (node (ref "J3") (pin "2") (pinfunction "2_2") (pintype "passive"))
      (node (ref "R106") (pin "1") (pinfunction "1_1") (pintype "passive"))
    )
    (net (code "41") (name "DC+") (class "Default")
      (node (ref "C51") (pin "2") (pinfunction "2_2") (pintype "passive"))
      (node (ref "D1") (pin "K") (pinfunction "K_K") (pintype "passive"))
      (node (ref "R105") (pin "1") (pinfunction "1_1") (pintype "passive"))
    )
    (net (code "42") (name "DGND") (class "Default")
      (node (ref "C35") (pin "1") (pinfunction "1_1") (pintype "passive"))
      (node (ref "C36") (pin "1") (pinfunction "1_1") (pintype "passive"))
      (node (ref "C50") (pin "1") (pinfunction "1_1") (pintype "passive"))
      (node (ref "DGND1") (pin "1") (pinfunction "1_1") (pintype "passive"))
      (node (ref "JP4") (pin "1") (pinfunction "1_1") (pintype "passive"))
      (node (ref "JP4") (pin "2") (pinfunction "2_2") (pintype "passive"))
      (node (ref "PC5") (pin "11") (pinfunction "E_11") (pintype "passive"))
      (node (ref "PC5") (pin "13") (pinfunction "E_13") (pintype "passive"))
      (node (ref "PC5") (pin "15") (pinfunction "E_15") (pintype "passive"))
      (node (ref "PC5") (pin "9") (pinfunction "E_9") (pintype "passive"))
      (node (ref "PC6") (pin "11") (pinfunction "E_11") (pintype "passive"))
      (node (ref "PC6") (pin "13") (pinfunction "E_13") (pintype "passive"))
      (node (ref "PC6") (pin "15") (pinfunction "E_15") (pintype "passive"))
      (node (ref "PC6") (pin "9") (pinfunction "E_9") (pintype "passive"))
      (node (ref "PC7") (pin "11") (pinfunction "E_11") (pintype "passive"))
      (node (ref "PC7") (pin "13") (pinfunction "E_13") (pintype "passive"))
      (node (ref "PC7") (pin "15") (pinfunction "E_15") (pintype "passive"))
      (node (ref "PC7") (pin "9") (pinfunction "E_9") (pintype "passive"))
      (node (ref "PC8") (pin "11") (pinfunction "E_11") (pintype "passive"))
      (node (ref "PC8") (pin "13") (pinfunction "E_13") (pintype "passive"))
      (node (ref "PC8") (pin "15") (pinfunction "E_15") (pintype "passive"))
      (node (ref "PC8") (pin "9") (pinfunction "E_9") (pintype "passive"))
      (node (ref "U6") (pin "10") (pinfunction "VSS_10") (pintype "power_in"))
      (node (ref "U6") (pin "16") (pinfunction "A1_16") (pintype "input"))
      (node (ref "U6") (pin "17") (pinfunction "A2_17") (pintype "input"))
    )
    (net (code "43") (name "EX24V") (class "Default")
      (node (ref "C33") (pin "2") (pinfunction "2_2") (pintype "passive"))
      (node (ref "C52") (pin "2") (pinfunction "2_2") (pintype "passive"))
      (node (ref "CN3") (pin "1") (pinfunction "1_1") (pintype "passive"))
      (node (ref "PC5") (pin "1") (pinfunction "A-LED_1") (pintype "passive"))
      (node (ref "PC5") (pin "3") (pinfunction "A-LED_3") (pintype "passive"))
      (node (ref "PC5") (pin "5") (pinfunction "A-LED_5") (pintype "passive"))
      (node (ref "PC5") (pin "7") (pinfunction "A-LED_7") (pintype "passive"))
      (node (ref "PC6") (pin "1") (pinfunction "A-LED_1") (pintype "passive"))
      (node (ref "PC6") (pin "3") (pinfunction "A-LED_3") (pintype "passive"))
      (node (ref "PC6") (pin "5") (pinfunction "A-LED_5") (pintype "passive"))
      (node (ref "PC6") (pin "7") (pinfunction "A-LED_7") (pintype "passive"))
      (node (ref "PC7") (pin "1") (pinfunction "A-LED_1") (pintype "passive"))
      (node (ref "PC7") (pin "3") (pinfunction "A-LED_3") (pintype "passive"))
      (node (ref "PC7") (pin "5") (pinfunction "A-LED_5") (pintype "passive"))
      (node (ref "PC7") (pin "7") (pinfunction "A-LED_7") (pintype "passive"))
      (node (ref "PC8") (pin "1") (pinfunction "A-LED_1") (pintype "passive"))
      (node (ref "PC8") (pin "3") (pinfunction "A-LED_3") (pintype "passive"))
      (node (ref "PC8") (pin "5") (pinfunction "A-LED_5") (pintype "passive"))
      (node (ref "PC8") (pin "7") (pinfunction "A-LED_7") (pintype "passive"))
      (node (ref "R100") (pin "2") (pinfunction "2_2") (pintype "passive"))
      (node (ref "R105") (pin "2") (pinfunction "2_2") (pintype "passive"))
      (node (ref "R72") (pin "2") (pinfunction "2_2") (pintype "passive"))
      (node (ref "R73") (pin "2") (pinfunction "2_2") (pintype "passive"))
      (node (ref "R76") (pin "2") (pinfunction "2_2") (pintype "passive"))
      (node (ref "R77") (pin "2") (pinfunction "2_2") (pintype "passive"))
      (node (ref "R80") (pin "2") (pinfunction "2_2") (pintype "passive"))
      (node (ref "R81") (pin "2") (pinfunction "2_2") (pintype "passive"))
      (node (ref "R84") (pin "2") (pinfunction "2_2") (pintype "passive"))
      (node (ref "R85") (pin "2") (pinfunction "2_2") (pintype "passive"))
      (node (ref "R88") (pin "2") (pinfunction "2_2") (pintype "passive"))
      (node (ref "R89") (pin "2") (pinfunction "2_2") (pintype "passive"))
      (node (ref "R92") (pin "2") (pinfunction "2_2") (pintype "passive"))
      (node (ref "R93") (pin "2") (pinfunction "2_2") (pintype "passive"))
      (node (ref "R96") (pin "2") (pinfunction "2_2") (pintype "passive"))
      (node (ref "R97") (pin "2") (pinfunction "2_2") (pintype "passive"))
    )
    (net (code "44") (name "EXGND") (class "Default")
      (node (ref "C32") (pin "1") (pinfunction "1_1") (pintype "passive"))
      (node (ref "C33") (pin "1") (pinfunction "1_1") (pintype "passive"))
      (node (ref "C34") (pin "1") (pinfunction "1_1") (pintype "passive"))
      (node (ref "C37") (pin "1") (pinfunction "1_1") (pintype "passive"))
      (node (ref "C38") (pin "1") (pinfunction "1_1") (pintype "passive"))
      (node (ref "C39") (pin "1") (pinfunction "1_1") (pintype "passive"))
      (node (ref "C40") (pin "1") (pinfunction "1_1") (pintype "passive"))
      (node (ref "C41") (pin "1") (pinfunction "1_1") (pintype "passive"))
      (node (ref "C42") (pin "1") (pinfunction "1_1") (pintype "passive"))
      (node (ref "C43") (pin "1") (pinfunction "1_1") (pintype "passive"))
      (node (ref "C44") (pin "1") (pinfunction "1_1") (pintype "passive"))
      (node (ref "C45") (pin "1") (pinfunction "1_1") (pintype "passive"))
      (node (ref "C46") (pin "1") (pinfunction "1_1") (pintype "passive"))
      (node (ref "C47") (pin "1") (pinfunction "1_1") (pintype "passive"))
      (node (ref "C48") (pin "1") (pinfunction "1_1") (pintype "passive"))
      (node (ref "C49") (pin "1") (pinfunction "1_1") (pintype "passive"))
      (node (ref "C52") (pin "1") (pinfunction "1_1") (pintype "passive"))
      (node (ref "CN3") (pin "2") (pinfunction "2_2") (pintype "passive"))
      (node (ref "EXT GND1") (pin "1") (pinfunction "1_1") (pintype "passive"))
      (node (ref "J1") (pin "16") (pinfunction "16_16") (pintype "passive"))
      (node (ref "J1") (pin "18") (pinfunction "18_18") (pintype "passive"))
      (node (ref "J3") (pin "12") (pinfunction "12_12") (pintype "passive"))
      (node (ref "JP3") (pin "1") (pinfunction "1_1") (pintype "passive"))
      (node (ref "JP3") (pin "2") (pinfunction "2_2") (pintype "passive"))
      (node (ref "R106") (pin "2") (pinfunction "2_2") (pintype "passive"))
    )
    (net (code "45") (name "Net-(D1-PadA)") (class "Default")
      (node (ref "D1") (pin "A") (pinfunction "A_A") (pintype "passive"))
      (node (ref "FUSE1") (pin "2") (pinfunction "2_2") (pintype "passive"))
    )
    (net (code "46") (name "Net-(FUSE1-Pad1)") (class "Default")
      (node (ref "FUSE1") (pin "1") (pinfunction "1_1") (pintype "passive"))
      (node (ref "J1") (pin "1") (pinfunction "1_1") (pintype "passive"))
      (node (ref "J3") (pin "1") (pinfunction "1_1") (pintype "passive"))
    )
    (net (code "47") (name "Net-(PC7-K-LED-Pad8)") (class "Default")
      (node (ref "PC7") (pin "8") (pinfunction "K-LED_8") (pintype "passive"))
      (node (ref "R102") (pin "2") (pinfunction "2_2") (pintype "passive"))
    )
    (net (code "48") (name "Net-(R102-Pad1)") (class "Default")
      (node (ref "R102") (pin "1") (pinfunction "1_1") (pintype "passive"))
      (node (ref "TP1") (pin "1") (pinfunction "1_1") (pintype "passive"))
    )
    (net (code "49") (name "Net-(U6-GPA0)") (class "Default")
      (node (ref "PC6") (pin "10") (pinfunction "C_10") (pintype "passive"))
      (node (ref "R67") (pin "1") (pinfunction "1_1") (pintype "passive"))
      (node (ref "U6") (pin "21") (pinfunction "GPA0_21") (pintype "passive"))
    )
    (net (code "50") (name "Net-(U6-GPA1)") (class "Default")
      (node (ref "PC6") (pin "12") (pinfunction "C_12") (pintype "passive"))
      (node (ref "R66") (pin "1") (pinfunction "1_1") (pintype "passive"))
      (node (ref "U6") (pin "22") (pinfunction "GPA1_22") (pintype "passive"))
    )
    (net (code "51") (name "Net-(U6-GPA2)") (class "Default")
      (node (ref "PC6") (pin "14") (pinfunction "C_14") (pintype "passive"))
      (node (ref "R65") (pin "1") (pinfunction "1_1") (pintype "passive"))
      (node (ref "U6") (pin "23") (pinfunction "GPA2_23") (pintype "passive"))
    )
    (net (code "52") (name "Net-(U6-GPA3)") (class "Default")
      (node (ref "PC6") (pin "16") (pinfunction "C_16") (pintype "passive"))
      (node (ref "R64") (pin "1") (pinfunction "1_1") (pintype "passive"))
      (node (ref "U6") (pin "24") (pinfunction "GPA3_24") (pintype "passive"))
    )
    (net (code "53") (name "Net-(U6-GPA4)") (class "Default")
      (node (ref "PC8") (pin "16") (pinfunction "C_16") (pintype "passive"))
      (node (ref "R68") (pin "1") (pinfunction "1_1") (pintype "passive"))
      (node (ref "U6") (pin "25") (pinfunction "GPA4_25") (pintype "passive"))
    )
    (net (code "54") (name "Net-(U6-GPA5)") (class "Default")
      (node (ref "PC8") (pin "14") (pinfunction "C_14") (pintype "passive"))
      (node (ref "R69") (pin "1") (pinfunction "1_1") (pintype "passive"))
      (node (ref "U6") (pin "26") (pinfunction "GPA5_26") (pintype "passive"))
    )
    (net (code "55") (name "Net-(U6-GPA6)") (class "Default")
      (node (ref "PC8") (pin "12") (pinfunction "C_12") (pintype "passive"))
      (node (ref "R70") (pin "1") (pinfunction "1_1") (pintype "passive"))
      (node (ref "U6") (pin "27") (pinfunction "GPA6_27") (pintype "passive"))
    )
    (net (code "56") (name "Net-(U6-GPA7)") (class "Default")
      (node (ref "PC8") (pin "10") (pinfunction "C_10") (pintype "passive"))
      (node (ref "R71") (pin "1") (pinfunction "1_1") (pintype "passive"))
      (node (ref "U6") (pin "28") (pinfunction "GPA7_28") (pintype "passive"))
    )
    (net (code "57") (name "Net-(U6-GPB0)") (class "Default")
      (node (ref "PC5") (pin "14") (pinfunction "C_14") (pintype "passive"))
      (node (ref "R58") (pin "1") (pinfunction "1_1") (pintype "passive"))
      (node (ref "U6") (pin "1") (pinfunction "GPB0_1") (pintype "passive"))
    )
    (net (code "58") (name "Net-(U6-GPB1)") (class "Default")
      (node (ref "PC5") (pin "16") (pinfunction "C_16") (pintype "passive"))
      (node (ref "R59") (pin "1") (pinfunction "1_1") (pintype "passive"))
      (node (ref "U6") (pin "2") (pinfunction "GPB1_2") (pintype "passive"))
    )
    (net (code "59") (name "Net-(U6-GPB2)") (class "Default")
      (node (ref "PC5") (pin "12") (pinfunction "C_12") (pintype "passive"))
      (node (ref "R57") (pin "1") (pinfunction "1_1") (pintype "passive"))
      (node (ref "U6") (pin "3") (pinfunction "GPB2_3") (pintype "passive"))
    )
    (net (code "60") (name "Net-(U6-GPB3)") (class "Default")
      (node (ref "PC5") (pin "10") (pinfunction "C_10") (pintype "passive"))
      (node (ref "R56") (pin "1") (pinfunction "1_1") (pintype "passive"))
      (node (ref "U6") (pin "4") (pinfunction "GPB3_4") (pintype "passive"))
    )
    (net (code "61") (name "Net-(U6-GPB4)") (class "Default")
      (node (ref "PC7") (pin "16") (pinfunction "C_16") (pintype "passive"))
      (node (ref "R63") (pin "1") (pinfunction "1_1") (pintype "passive"))
      (node (ref "U6") (pin "5") (pinfunction "GPB4_5") (pintype "passive"))
    )
    (net (code "62") (name "Net-(U6-GPB5)") (class "Default")
      (node (ref "PC7") (pin "14") (pinfunction "C_14") (pintype "passive"))
      (node (ref "R62") (pin "1") (pinfunction "1_1") (pintype "passive"))
      (node (ref "U6") (pin "6") (pinfunction "GPB5_6") (pintype "passive"))
    )
    (net (code "63") (name "Net-(U6-GPB6)") (class "Default")
      (node (ref "PC7") (pin "12") (pinfunction "C_12") (pintype "passive"))
      (node (ref "R61") (pin "1") (pinfunction "1_1") (pintype "passive"))
      (node (ref "U6") (pin "7") (pinfunction "GPB6_7") (pintype "passive"))
    )
    (net (code "64") (name "Net-(U6-GPB7)") (class "Default")
      (node (ref "PC7") (pin "10") (pinfunction "C_10") (pintype "passive"))
      (node (ref "R60") (pin "1") (pinfunction "1_1") (pintype "passive"))
      (node (ref "U6") (pin "8") (pinfunction "GPB7_8") (pintype "passive"))
    )
    (net (code "65") (name "unconnected-(U6-INTB-Pad19)") (class "Default")
      (node (ref "U6") (pin "19") (pinfunction "INTB_19") (pintype "output+no_connect"))
    )
    (net (code "66") (name "unconnected-(U6-NC(SO)-Pad14)") (class "Default")
      (node (ref "U6") (pin "14") (pinfunction "NC(SO)_14") (pintype "passive"))
    )
    (net (code "67") (name "unconnected-(U6-NC(~{CS})-Pad11)") (class "Default")
      (node (ref "U6") (pin "11") (pinfunction "NC(~{CS})_11") (pintype "passive+no_connect"))
    )
  )
)
